# rc_rx_5V_rotors_only.net
KiCad netlist of a schematic drawn in EAGLE
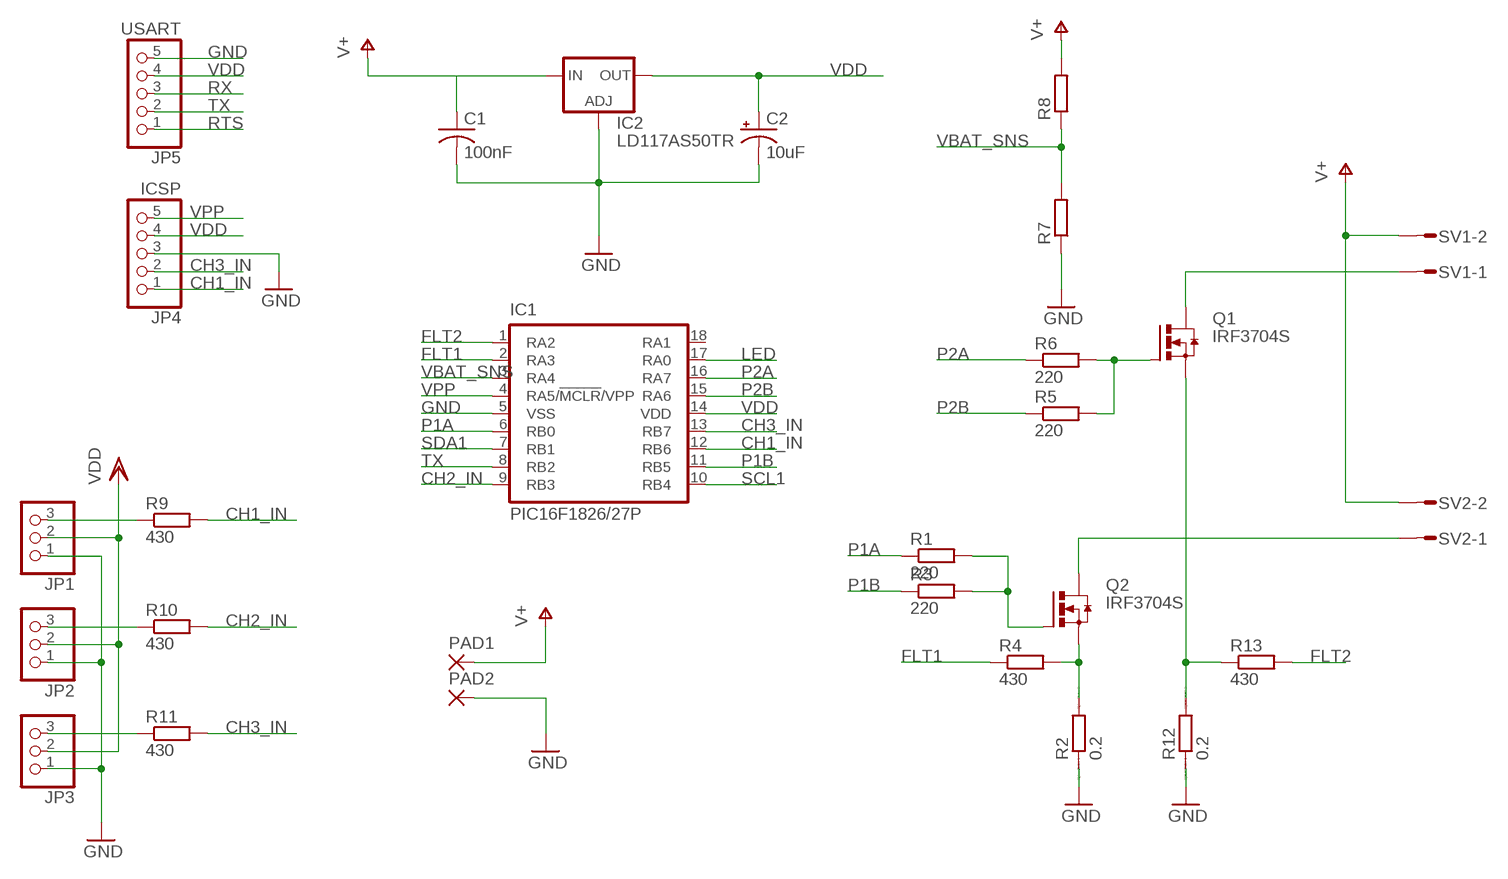
[diagram p0: schematic, sheet 1]

(export (version "E")
  (design (tool "Eeschema 10.0.6"))
  (components
    (comp (ref "C1")
      (value "100nF")
      (footprint "eagle-import:C025-025X050")
      (libsource (lib "eagle-import") (part "C-US025-025X050"))
    )
    (comp (ref "C2")
      (value "10uF")
      (footprint "eagle-import:E3,5-8")
      (libsource (lib "eagle-import") (part "CPOL-USE3.5-8"))
    )
    (comp (ref "IC1")
      (value "PIC16F1826/27P")
      (footprint "eagle-import:DIL18")
      (libsource (lib "eagle-import") (part "PIC16F1826/27P"))
    )
    (comp (ref "IC2")
      (value "LD117AS50TR")
      (footprint "eagle-import:SOT223")
      (libsource (lib "eagle-import") (part "LD117A?S50TR"))
    )
    (comp (ref "JP1")
      (value "PINHD-1X3")
      (footprint "eagle-import:1X03")
      (libsource (lib "eagle-import") (part "PINHD-1X3"))
    )
    (comp (ref "JP2")
      (value "PINHD-1X3")
      (footprint "eagle-import:1X03")
      (libsource (lib "eagle-import") (part "PINHD-1X3"))
    )
    (comp (ref "JP3")
      (value "PINHD-1X3")
      (footprint "eagle-import:1X03")
      (libsource (lib "eagle-import") (part "PINHD-1X3"))
    )
    (comp (ref "JP4")
      (value "ICSP")
      (footprint "eagle-import:1X05")
      (libsource (lib "eagle-import") (part "PINHD-1X5"))
    )
    (comp (ref "JP5")
      (value "USART")
      (footprint "eagle-import:1X05")
      (libsource (lib "eagle-import") (part "PINHD-1X5"))
    )
    (comp (ref "PAD1")
      (value "3,81/1,4")
      (footprint "eagle-import:3,81_1,4")
      (libsource (lib "eagle-import") (part "3,81/1,4"))
    )
    (comp (ref "PAD2")
      (value "3,81/1,4")
      (footprint "eagle-import:3,81_1,4")
      (libsource (lib "eagle-import") (part "3,81/1,4"))
    )
    (comp (ref "Q1")
      (value "IRF3704S")
      (footprint "eagle-import:D2PACK")
      (libsource (lib "eagle-import") (part "IRF3704S"))
    )
    (comp (ref "Q2")
      (value "IRF3704S")
      (footprint "eagle-import:D2PACK")
      (libsource (lib "eagle-import") (part "IRF3704S"))
    )
    (comp (ref "R1")
      (value "220")
      (footprint "eagle-import:0204_7")
      (libsource (lib "eagle-import") (part "R-EU_0204/7"))
    )
    (comp (ref "R2")
      (value "0.2")
      (footprint "eagle-import:R1210")
      (libsource (lib "eagle-import") (part "RR1210"))
    )
    (comp (ref "R3")
      (value "220")
      (footprint "eagle-import:0204_7")
      (libsource (lib "eagle-import") (part "R-EU_0204/7"))
    )
    (comp (ref "R4")
      (value "430")
      (footprint "eagle-import:0204_7")
      (libsource (lib "eagle-import") (part "R-EU_0204/7"))
    )
    (comp (ref "R5")
      (value "220")
      (footprint "eagle-import:0204_7")
      (libsource (lib "eagle-import") (part "R-EU_0204/7"))
    )
    (comp (ref "R6")
      (value "220")
      (footprint "eagle-import:0204_7")
      (libsource (lib "eagle-import") (part "R-EU_0204/7"))
    )
    (comp (ref "R7")
      (value "R-EU_0204/7")
      (footprint "eagle-import:0204_7")
      (libsource (lib "eagle-import") (part "R-EU_0204/7"))
    )
    (comp (ref "R8")
      (value "R-EU_0204/7")
      (footprint "eagle-import:0204_7")
      (libsource (lib "eagle-import") (part "R-EU_0204/7"))
    )
    (comp (ref "R9")
      (value "430")
      (footprint "eagle-import:0204_7")
      (libsource (lib "eagle-import") (part "R-EU_0204/7"))
    )
    (comp (ref "R10")
      (value "430")
      (footprint "eagle-import:0204_7")
      (libsource (lib "eagle-import") (part "R-EU_0204/7"))
    )
    (comp (ref "R11")
      (value "430")
      (footprint "eagle-import:0204_7")
      (libsource (lib "eagle-import") (part "R-EU_0204/7"))
    )
    (comp (ref "R12")
      (value "0.2")
      (footprint "eagle-import:R1210")
      (libsource (lib "eagle-import") (part "RR1210"))
    )
    (comp (ref "R13")
      (value "430")
      (footprint "eagle-import:0204_7")
      (libsource (lib "eagle-import") (part "R-EU_0204/7"))
    )
    (comp (ref "SV1")
      (value "S02P")
      (footprint "eagle-import:S02P")
      (libsource (lib "eagle-import") (part "S02P"))
    )
    (comp (ref "SV2")
      (value "S02P")
      (footprint "eagle-import:S02P")
      (libsource (lib "eagle-import") (part "S02P"))
    )
  )
  (nets
    (net (code "1") (name "/CH1_IN") (class "Default")
      (node (ref "IC1") (pin "12") (pinfunction "RB6_12") (pintype "bidirectional"))
      (node (ref "JP4") (pin "1") (pinfunction "1_1") (pintype "passive"))
      (node (ref "R9") (pin "2") (pinfunction "2_2") (pintype "passive"))
    )
    (net (code "2") (name "/CH2_IN") (class "Default")
      (node (ref "IC1") (pin "9") (pinfunction "RB3_9") (pintype "bidirectional"))
      (node (ref "R10") (pin "2") (pinfunction "2_2") (pintype "passive"))
    )
    (net (code "3") (name "/CH3_IN") (class "Default")
      (node (ref "IC1") (pin "13") (pinfunction "RB7_13") (pintype "bidirectional"))
      (node (ref "JP4") (pin "2") (pinfunction "2_2") (pintype "passive"))
      (node (ref "R11") (pin "2") (pinfunction "2_2") (pintype "passive"))
    )
    (net (code "4") (name "/FLT1") (class "Default")
      (node (ref "IC1") (pin "2") (pinfunction "RA3_2") (pintype "bidirectional"))
      (node (ref "R4") (pin "1") (pinfunction "1_1") (pintype "passive"))
    )
    (net (code "5") (name "/FLT2") (class "Default")
      (node (ref "IC1") (pin "1") (pinfunction "RA2_1") (pintype "bidirectional"))
      (node (ref "R13") (pin "2") (pinfunction "2_2") (pintype "passive"))
    )
    (net (code "6") (name "/LED") (class "Default")
      (node (ref "IC1") (pin "17") (pinfunction "RA0_17") (pintype "bidirectional"))
    )
    (net (code "7") (name "/P1A") (class "Default")
      (node (ref "IC1") (pin "6") (pinfunction "RB0_6") (pintype "bidirectional"))
      (node (ref "R1") (pin "1") (pinfunction "1_1") (pintype "passive"))
    )
    (net (code "8") (name "/P1B") (class "Default")
      (node (ref "IC1") (pin "11") (pinfunction "RB5_11") (pintype "bidirectional"))
      (node (ref "R3") (pin "1") (pinfunction "1_1") (pintype "passive"))
    )
    (net (code "9") (name "/P2A") (class "Default")
      (node (ref "IC1") (pin "16") (pinfunction "RA7_16") (pintype "bidirectional"))
      (node (ref "R6") (pin "1") (pinfunction "1_1") (pintype "passive"))
    )
    (net (code "10") (name "/P2B") (class "Default")
      (node (ref "IC1") (pin "15") (pinfunction "RA6_15") (pintype "bidirectional"))
      (node (ref "R5") (pin "1") (pinfunction "1_1") (pintype "passive"))
    )
    (net (code "11") (name "/RTS") (class "Default")
      (node (ref "JP5") (pin "1") (pinfunction "1_1") (pintype "passive"))
    )
    (net (code "12") (name "/RX") (class "Default")
      (node (ref "JP5") (pin "3") (pinfunction "3_3") (pintype "passive"))
    )
    (net (code "13") (name "/SCL1") (class "Default")
      (node (ref "IC1") (pin "10") (pinfunction "RB4_10") (pintype "bidirectional"))
    )
    (net (code "14") (name "/SDA1") (class "Default")
      (node (ref "IC1") (pin "7") (pinfunction "RB1_7") (pintype "bidirectional"))
    )
    (net (code "15") (name "/TX") (class "Default")
      (node (ref "IC1") (pin "8") (pinfunction "RB2_8") (pintype "bidirectional"))
      (node (ref "JP5") (pin "2") (pinfunction "2_2") (pintype "passive"))
    )
    (net (code "16") (name "/VBAT_SNS") (class "Default")
      (node (ref "IC1") (pin "3") (pinfunction "RA4_3") (pintype "bidirectional"))
      (node (ref "R7") (pin "2") (pinfunction "2_2") (pintype "passive"))
      (node (ref "R8") (pin "1") (pinfunction "1_1") (pintype "passive"))
    )
    (net (code "17") (name "/VPP") (class "Default")
      (node (ref "IC1") (pin "4") (pinfunction "RA5/~{MCLR}/VPP_4") (pintype "bidirectional"))
      (node (ref "JP4") (pin "5") (pinfunction "5_5") (pintype "passive"))
    )
    (net (code "18") (name "GND") (class "Default")
      (node (ref "C1") (pin "2") (pinfunction "2_2") (pintype "passive"))
      (node (ref "C2") (pin "-") (pinfunction "-_-") (pintype "passive"))
      (node (ref "IC1") (pin "5") (pinfunction "VSS_5") (pintype "power_in"))
      (node (ref "IC2") (pin "1") (pinfunction "ADJ_1") (pintype "input"))
      (node (ref "JP1") (pin "1") (pinfunction "1_1") (pintype "passive"))
      (node (ref "JP2") (pin "1") (pinfunction "1_1") (pintype "passive"))
      (node (ref "JP3") (pin "1") (pinfunction "1_1") (pintype "passive"))
      (node (ref "JP4") (pin "3") (pinfunction "3_3") (pintype "passive"))
      (node (ref "JP5") (pin "5") (pinfunction "5_5") (pintype "passive"))
      (node (ref "PAD2") (pin "1") (pinfunction "P_1") (pintype "passive"))
      (node (ref "R12") (pin "1") (pinfunction "1_1") (pintype "passive"))
      (node (ref "R2") (pin "1") (pinfunction "1_1") (pintype "passive"))
      (node (ref "R7") (pin "1") (pinfunction "1_1") (pintype "passive"))
    )
    (net (code "19") (name "Net-(JP1-Pad3)") (class "Default")
      (node (ref "JP1") (pin "3") (pinfunction "3_3") (pintype "passive"))
      (node (ref "R9") (pin "1") (pinfunction "1_1") (pintype "passive"))
    )
    (net (code "20") (name "Net-(JP2-Pad3)") (class "Default")
      (node (ref "JP2") (pin "3") (pinfunction "3_3") (pintype "passive"))
      (node (ref "R10") (pin "1") (pinfunction "1_1") (pintype "passive"))
    )
    (net (code "21") (name "Net-(JP3-Pad3)") (class "Default")
      (node (ref "JP3") (pin "3") (pinfunction "3_3") (pintype "passive"))
      (node (ref "R11") (pin "1") (pinfunction "1_1") (pintype "passive"))
    )
    (net (code "22") (name "Net-(Q1-D)") (class "Default")
      (node (ref "Q1") (pin "2") (pinfunction "D_2") (pintype "passive"))
      (node (ref "SV1") (pin "1") (pinfunction "S_1") (pintype "passive"))
    )
    (net (code "23") (name "Net-(Q1-G)") (class "Default")
      (node (ref "Q1") (pin "1") (pinfunction "G_1") (pintype "passive"))
      (node (ref "R5") (pin "2") (pinfunction "2_2") (pintype "passive"))
      (node (ref "R6") (pin "2") (pinfunction "2_2") (pintype "passive"))
    )
    (net (code "24") (name "Net-(Q1-S)") (class "Default")
      (node (ref "Q1") (pin "3") (pinfunction "S_3") (pintype "passive"))
      (node (ref "R12") (pin "2") (pinfunction "2_2") (pintype "passive"))
      (node (ref "R13") (pin "1") (pinfunction "1_1") (pintype "passive"))
    )
    (net (code "25") (name "Net-(Q2-D)") (class "Default")
      (node (ref "Q2") (pin "2") (pinfunction "D_2") (pintype "passive"))
      (node (ref "SV2") (pin "1") (pinfunction "S_1") (pintype "passive"))
    )
    (net (code "26") (name "Net-(Q2-G)") (class "Default")
      (node (ref "Q2") (pin "1") (pinfunction "G_1") (pintype "passive"))
      (node (ref "R1") (pin "2") (pinfunction "2_2") (pintype "passive"))
      (node (ref "R3") (pin "2") (pinfunction "2_2") (pintype "passive"))
    )
    (net (code "27") (name "Net-(Q2-S)") (class "Default")
      (node (ref "Q2") (pin "3") (pinfunction "S_3") (pintype "passive"))
      (node (ref "R2") (pin "2") (pinfunction "2_2") (pintype "passive"))
      (node (ref "R4") (pin "2") (pinfunction "2_2") (pintype "passive"))
    )
    (net (code "28") (name "V+") (class "Default")
      (node (ref "C1") (pin "1") (pinfunction "1_1") (pintype "passive"))
      (node (ref "IC2") (pin "3") (pinfunction "IN_3") (pintype "input"))
      (node (ref "PAD1") (pin "1") (pinfunction "P_1") (pintype "passive"))
      (node (ref "R8") (pin "2") (pinfunction "2_2") (pintype "passive"))
      (node (ref "SV1") (pin "2") (pinfunction "S_2") (pintype "passive"))
      (node (ref "SV2") (pin "2") (pinfunction "S_2") (pintype "passive"))
    )
    (net (code "29") (name "VDD") (class "Default")
      (node (ref "C2") (pin "+") (pinfunction "+_+") (pintype "passive"))
      (node (ref "IC1") (pin "14") (pinfunction "VDD_14") (pintype "power_in"))
      (node (ref "IC2") (pin "4") (pinfunction "OUT_4") (pintype "passive"))
      (node (ref "JP1") (pin "2") (pinfunction "2_2") (pintype "passive"))
      (node (ref "JP2") (pin "2") (pinfunction "2_2") (pintype "passive"))
      (node (ref "JP3") (pin "2") (pinfunction "2_2") (pintype "passive"))
      (node (ref "JP4") (pin "4") (pinfunction "4_4") (pintype "passive"))
      (node (ref "JP5") (pin "4") (pinfunction "4_4") (pintype "passive"))
    )
    (net (code "30") (name "unconnected-(IC1-RA1-Pad18)") (class "Default")
      (node (ref "IC1") (pin "18") (pinfunction "RA1_18") (pintype "bidirectional"))
    )
  )
)
